# SparkInterfaceBreadboardSupplement_v1.net
KiCad netlist of a schematic drawn in EAGLE
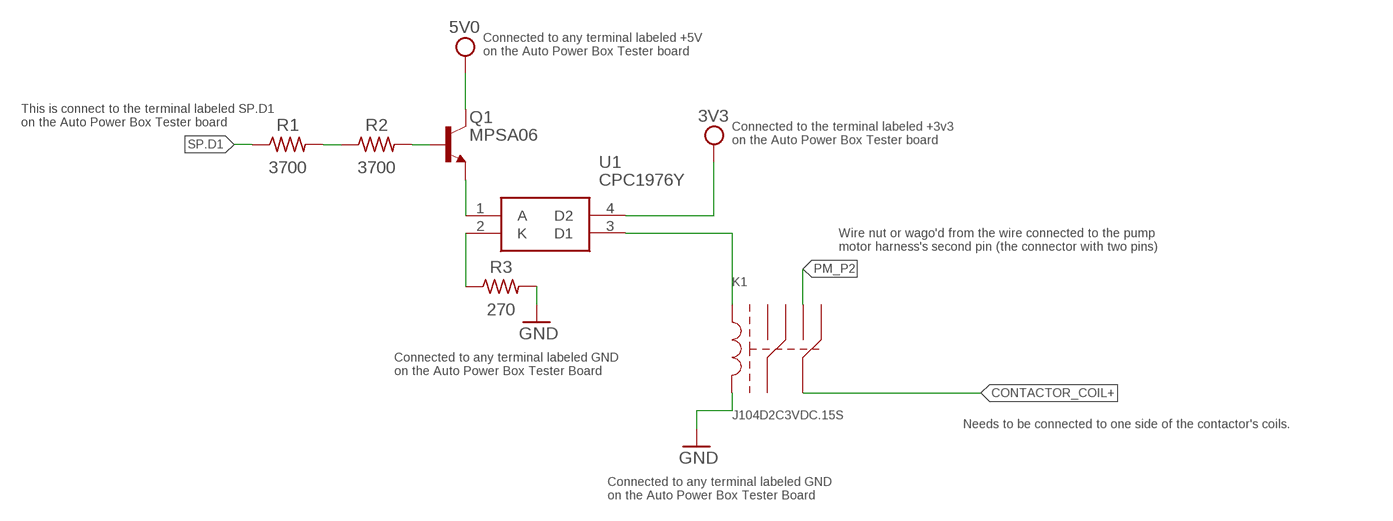
[diagram p0: schematic, sheet 1]

(export (version "E")
  (design (tool "Eeschema 10.0.6"))
  (components
    (comp (ref "K1")
      (value "J104D2C3VDC.15S")
      (footprint "eagle-import:J104D2C3VDC.15S")
      (libsource (lib "eagle-import") (part "J104D2C3VDC.15S"))
    )
    (comp (ref "Q1")
      (value "MPSA06")
      (footprint "eagle-import:TO92")
      (fields (field (name "MANUFACTURER") "Onsemi") (field (name "MPN") "BC549"))
      (libsource (lib "eagle-import") (part "NPN__TO92-CBEBC549"))
    )
    (comp (ref "R1")
      (value "3700")
      (footprint "eagle-import:RESAD724W46L381D178B")
      (libsource (lib "eagle-import") (part "R-USAXIAL-7.2MM-PITCH_"))
    )
    (comp (ref "R2")
      (value "3700")
      (footprint "eagle-import:RESAD724W46L381D178B")
      (libsource (lib "eagle-import") (part "R-USAXIAL-7.2MM-PITCH_"))
    )
    (comp (ref "R3")
      (value "270")
      (footprint "eagle-import:RESAD724W46L381D178B")
      (libsource (lib "eagle-import") (part "R-USAXIAL-7.2MM-PITCH_"))
    )
    (comp (ref "U1")
      (value "CPC1976Y")
      (footprint "eagle-import:SOP254P962X315-4N")
      (fields
        (field (name "ARROW_PART_NUMBER") "AQY212GHAX")
        (field (name "MOUSER_PART_NUMBER") "667-AQY212GHAX")
      )
      (libsource (lib "eagle-import") (part "AQY212GHAX"))
    )
  )
  (nets
    (net (code "1") (name "3V3") (class "Default")
      (node (ref "U1") (pin "4") (pinfunction "D2_4") (pintype "bidirectional"))
    )
    (net (code "2") (name "5V0") (class "Default")
      (node (ref "Q1") (pin "1") (pinfunction "C_1") (pintype "passive"))
    )
    (net (code "3") (name "CONTACTOR_COIL+") (class "Default")
      (node (ref "K1") (pin "4") (pinfunction "C2_4") (pintype "bidirectional"))
    )
    (net (code "4") (name "GND") (class "Default")
      (node (ref "K1") (pin "1") (pinfunction "LA_1") (pintype "bidirectional"))
      (node (ref "R3") (pin "2") (pinfunction "2_2") (pintype "passive"))
    )
    (net (code "5") (name "Net-(K1-LB)") (class "Default")
      (node (ref "K1") (pin "2") (pinfunction "LB_2") (pintype "bidirectional"))
      (node (ref "U1") (pin "3") (pinfunction "D1_3") (pintype "bidirectional"))
    )
    (net (code "6") (name "Net-(Q1-B)") (class "Default")
      (node (ref "Q1") (pin "2") (pinfunction "B_2") (pintype "passive"))
      (node (ref "R2") (pin "2") (pinfunction "2_2") (pintype "passive"))
    )
    (net (code "7") (name "Net-(Q1-E)") (class "Default")
      (node (ref "Q1") (pin "3") (pinfunction "E_3") (pintype "passive"))
      (node (ref "U1") (pin "1") (pinfunction "A_1") (pintype "bidirectional"))
    )
    (net (code "8") (name "Net-(R1-Pad2)") (class "Default")
      (node (ref "R1") (pin "2") (pinfunction "2_2") (pintype "passive"))
      (node (ref "R2") (pin "1") (pinfunction "1_1") (pintype "passive"))
    )
    (net (code "9") (name "Net-(U1-K)") (class "Default")
      (node (ref "R3") (pin "1") (pinfunction "1_1") (pintype "passive"))
      (node (ref "U1") (pin "2") (pinfunction "K_2") (pintype "bidirectional"))
    )
    (net (code "10") (name "PM_P2") (class "Default")
      (node (ref "K1") (pin "8") (pinfunction "NO2_8") (pintype "bidirectional"))
    )
    (net (code "11") (name "SP.D1") (class "Default")
      (node (ref "R1") (pin "1") (pinfunction "1_1") (pintype "passive"))
    )
    (net (code "12") (name "unconnected-(K1-C1-Pad3)") (class "Default")
      (node (ref "K1") (pin "3") (pinfunction "C1_3") (pintype "bidirectional"))
    )
    (net (code "13") (name "unconnected-(K1-NC1-Pad5)") (class "Default")
      (node (ref "K1") (pin "5") (pinfunction "NC1_5") (pintype "bidirectional"))
    )
    (net (code "14") (name "unconnected-(K1-NC2-Pad6)") (class "Default")
      (node (ref "K1") (pin "6") (pinfunction "NC2_6") (pintype "bidirectional"))
    )
    (net (code "15") (name "unconnected-(K1-NO1-Pad7)") (class "Default")
      (node (ref "K1") (pin "7") (pinfunction "NO1_7") (pintype "bidirectional"))
    )
  )
)
